# BLDC-M8.net
KiCad netlist of a schematic drawn in Altium Designer
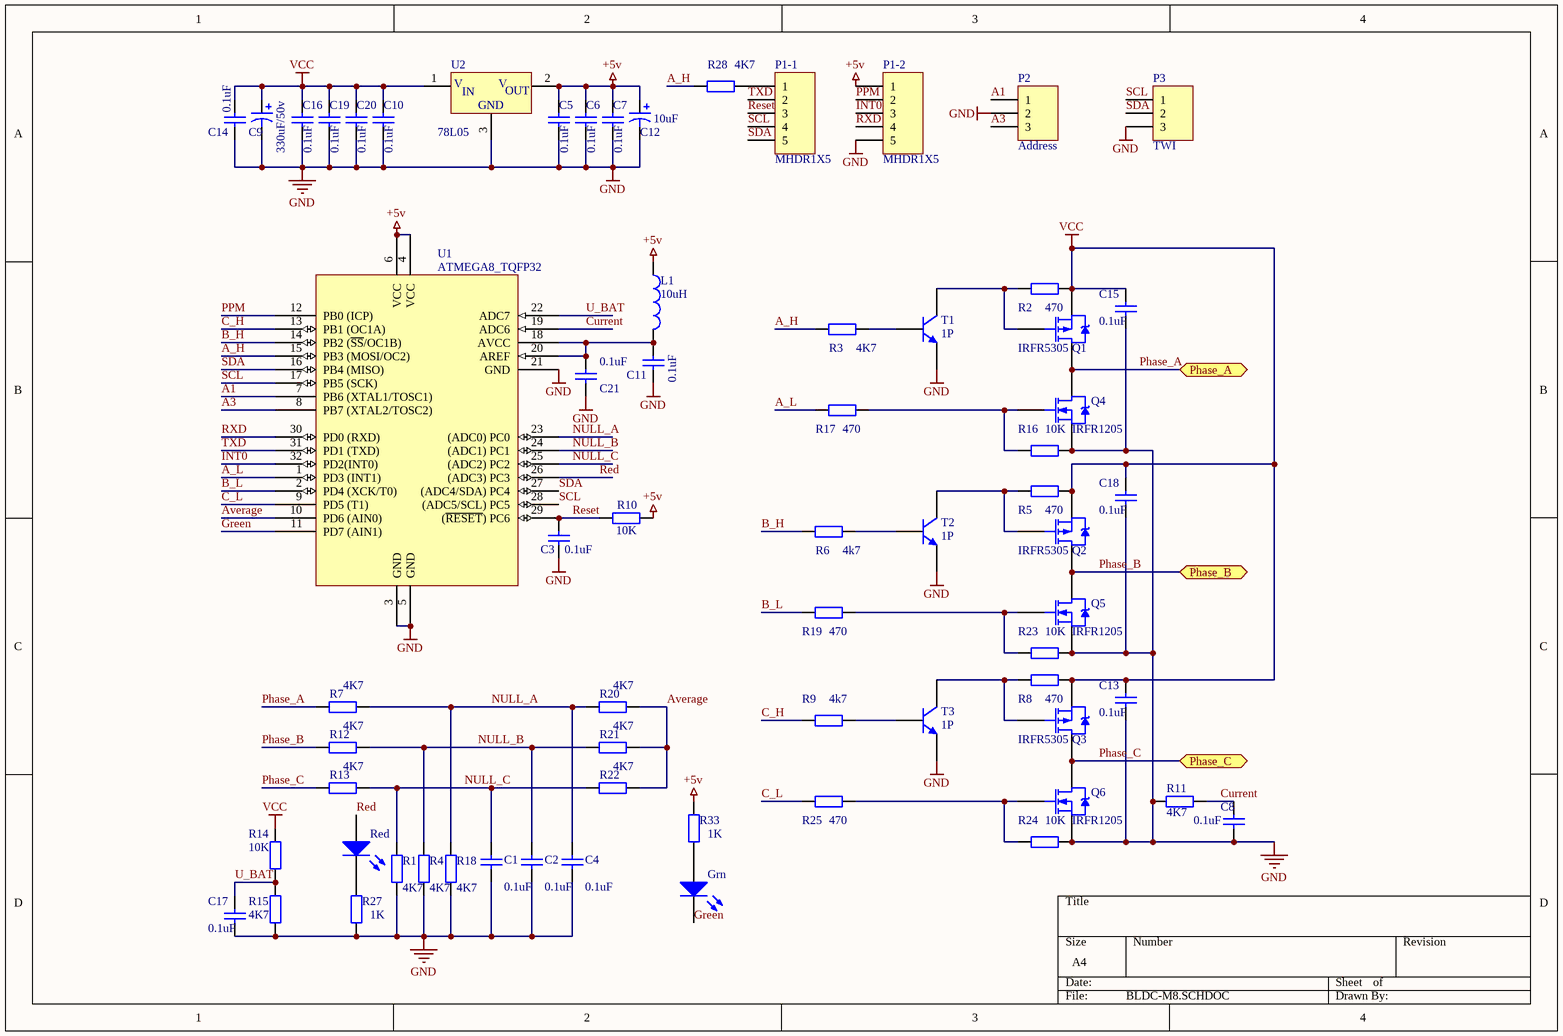
[diagram p0: BLDC-M8.SCHDOC]

(export (version "E")
  (design (tool "Eeschema 10.0.6"))
  (components
    (comp (ref "C1")
      (value "0.1uF")
      (footprint "1608[0603]")
      (description "Capacitor")
      (fields (field (name "Comment") "Cap") (field (name "PUBLISHER") "Altium Limited"))
      (libsource (lib "Miscellaneous Devices") (part "Cap"))
    )
    (comp (ref "C2")
      (value "0.1uF")
      (footprint "1608[0603]")
      (description "Capacitor")
      (fields (field (name "Comment") "Cap") (field (name "PUBLISHER") "Altium Limited"))
      (libsource (lib "Miscellaneous Devices") (part "Cap"))
    )
    (comp (ref "C3")
      (value "0.1uF")
      (footprint "1608[0603]")
      (description "Capacitor")
      (fields (field (name "Comment") "Cap") (field (name "PUBLISHER") "Altium Limited"))
      (libsource (lib "Miscellaneous Devices") (part "Cap"))
    )
    (comp (ref "C4")
      (value "0.1uF")
      (footprint "1608[0603]")
      (description "Capacitor")
      (fields (field (name "Comment") "Cap") (field (name "PUBLISHER") "Altium Limited"))
      (libsource (lib "Miscellaneous Devices") (part "Cap"))
    )
    (comp (ref "C5")
      (value "0.1uF")
      (footprint "1608[0603]")
      (description "Capacitor")
      (fields (field (name "Comment") "Cap") (field (name "PUBLISHER") "Altium Limited"))
      (libsource (lib "Miscellaneous Devices") (part "Cap"))
    )
    (comp (ref "C6")
      (value "0.1uF")
      (footprint "1608[0603]")
      (description "Capacitor")
      (fields (field (name "Comment") "Cap") (field (name "PUBLISHER") "Altium Limited"))
      (libsource (lib "Miscellaneous Devices") (part "Cap"))
    )
    (comp (ref "C7")
      (value "0.1uF")
      (footprint "1608[0603]")
      (description "Capacitor")
      (fields (field (name "Comment") "Cap") (field (name "PUBLISHER") "Altium Limited"))
      (libsource (lib "Miscellaneous Devices") (part "Cap"))
    )
    (comp (ref "C8")
      (value "0.1uF")
      (footprint "1608[0603]")
      (description "Capacitor")
      (fields (field (name "Comment") "Cap") (field (name "PUBLISHER") "Altium Limited"))
      (libsource (lib "Miscellaneous Devices") (part "Cap"))
    )
    (comp (ref "C9")
      (value "330uF/50v")
      (footprint "RAD-0.2")
      (description "Polarized Capacitor (Radial)")
      (fields (field (name "Comment") "Cap Pol1") (field (name "PUBLISHER") "Altium Limited"))
      (libsource (lib "Miscellaneous Devices") (part "Cap Pol1"))
    )
    (comp (ref "C10")
      (value "0.1uF")
      (footprint "1608[0603]")
      (description "Capacitor")
      (fields (field (name "Comment") "Cap") (field (name "PUBLISHER") "Altium Limited"))
      (libsource (lib "Miscellaneous Devices") (part "Cap"))
    )
    (comp (ref "C11")
      (value "0.1uF")
      (footprint "1608[0603]")
      (description "Capacitor")
      (fields (field (name "Comment") "Cap") (field (name "PUBLISHER") "Altium Limited"))
      (libsource (lib "Miscellaneous Devices") (part "Cap"))
    )
    (comp (ref "C12")
      (value "10uF")
      (footprint "3216[1206]")
      (description "Polarized Capacitor (Radial)")
      (fields (field (name "Comment") "Cap Pol1") (field (name "PUBLISHER") "Altium Limited"))
      (libsource (lib "Miscellaneous Devices") (part "Cap Pol1"))
    )
    (comp (ref "C13")
      (value "0.1uF")
      (footprint "1608[0603]")
      (description "Capacitor")
      (fields (field (name "Comment") "Cap") (field (name "PUBLISHER") "Altium Limited"))
      (libsource (lib "Miscellaneous Devices") (part "Cap"))
    )
    (comp (ref "C14")
      (value "0.1uF")
      (footprint "1608[0603]")
      (description "Capacitor")
      (fields (field (name "Comment") "Cap") (field (name "PUBLISHER") "Altium Limited"))
      (libsource (lib "Miscellaneous Devices") (part "Cap"))
    )
    (comp (ref "C15")
      (value "0.1uF")
      (footprint "1608[0603]")
      (description "Capacitor")
      (fields (field (name "Comment") "Cap") (field (name "PUBLISHER") "Altium Limited"))
      (libsource (lib "Miscellaneous Devices") (part "Cap"))
    )
    (comp (ref "C16")
      (value "0.1uF")
      (footprint "1608[0603]")
      (description "Capacitor")
      (fields (field (name "Comment") "Cap") (field (name "PUBLISHER") "Altium Limited"))
      (libsource (lib "Miscellaneous Devices") (part "Cap"))
    )
    (comp (ref "C17")
      (value "0.1uF")
      (footprint "1608[0603]")
      (description "Capacitor")
      (fields (field (name "Comment") "Cap") (field (name "PUBLISHER") "Altium Limited"))
      (libsource (lib "Miscellaneous Devices") (part "Cap"))
    )
    (comp (ref "C18")
      (value "0.1uF")
      (footprint "1608[0603]")
      (description "Capacitor")
      (fields (field (name "Comment") "Cap") (field (name "PUBLISHER") "Altium Limited"))
      (libsource (lib "Miscellaneous Devices") (part "Cap"))
    )
    (comp (ref "C19")
      (value "0.1uF")
      (footprint "1608[0603]")
      (description "Capacitor")
      (fields (field (name "Comment") "Cap") (field (name "PUBLISHER") "Altium Limited"))
      (libsource (lib "Miscellaneous Devices") (part "Cap"))
    )
    (comp (ref "C20")
      (value "0.1uF")
      (footprint "1608[0603]")
      (description "Capacitor")
      (fields (field (name "Comment") "Cap") (field (name "PUBLISHER") "Altium Limited"))
      (libsource (lib "Miscellaneous Devices") (part "Cap"))
    )
    (comp (ref "C21")
      (value "0.1uF")
      (footprint "1608[0603]")
      (description "Capacitor")
      (fields (field (name "Comment") "Cap") (field (name "PUBLISHER") "Altium Limited"))
      (libsource (lib "Miscellaneous Devices") (part "Cap"))
    )
    (comp (ref "Grn")
      (value "LED0")
      (footprint "1608[0603]")
      (description "Typical INFRARED GaAs LED")
      (fields (field (name "PUBLISHER") "Altium Limited"))
      (libsource (lib "Miscellaneous Devices") (part "LED0"))
    )
    (comp (ref "L1")
      (value "10uH")
      (footprint "0402-A")
      (description "Inductor")
      (fields (field (name "PUBLISHER") "Altium Limited"))
      (libsource (lib "Miscellaneous Devices") (part "Inductor"))
    )
    (comp (ref "P1-1")
      (value "MHDR1X5")
      (footprint "MHDR1X5")
      (description "Header, 5-Pin")
      (fields (field (name "PUBLISHER") "Altium Limited"))
      (libsource (lib "Miscellaneous Connectors") (part "MHDR1X5"))
    )
    (comp (ref "P1-2")
      (value "MHDR1X5")
      (footprint "MHDR1X5")
      (description "Header, 5-Pin")
      (fields (field (name "PUBLISHER") "Altium Limited"))
      (libsource (lib "Miscellaneous Connectors") (part "MHDR1X5"))
    )
    (comp (ref "P2")
      (value "Address")
      (footprint "HDR1X3")
      (description "Header, 3-Pin")
      (fields (field (name "PUBLISHER") "Altium Limited"))
      (libsource (lib "Miscellaneous Connectors") (part "Header 3"))
    )
    (comp (ref "P3")
      (value "TWI")
      (footprint "HDR1X3")
      (description "Header, 3-Pin")
      (fields (field (name "PUBLISHER") "Altium Limited"))
      (libsource (lib "Miscellaneous Connectors") (part "Header 3"))
    )
    (comp (ref "Q1")
      (value "IRFR5305")
      (footprint "TO-252AA")
      (description "HEXFET Power MOSFET")
      (fields
        (field (name "MANUFACTURER") "International Rectifier")
        (field (name "PUBLISHER") "Altium Limited")
      )
      (libsource (lib "IR Discrete MOSFET") (part "IRFR5305"))
    )
    (comp (ref "Q2")
      (value "IRFR5305")
      (footprint "SIP-G3/E8")
      (description "HEXFET Power MOSFET")
      (fields
        (field (name "MANUFACTURER") "International Rectifier")
        (field (name "PUBLISHER") "Altium Limited")
      )
      (libsource (lib "IR Discrete MOSFET") (part "IRFR5305"))
    )
    (comp (ref "Q3")
      (value "IRFR5305")
      (footprint "SIP-G3/E8")
      (description "HEXFET Power MOSFET")
      (fields
        (field (name "MANUFACTURER") "International Rectifier")
        (field (name "PUBLISHER") "Altium Limited")
      )
      (libsource (lib "IR Discrete MOSFET") (part "IRFR5305"))
    )
    (comp (ref "Q4")
      (value "IRFR1205")
      (footprint "SIP-G3/E8")
      (description "HEXFET Power MOSFET")
      (fields
        (field (name "MANUFACTURER") "International Rectifier")
        (field (name "PUBLISHER") "Altium Limited")
      )
      (libsource (lib "IR Discrete MOSFET") (part "IRFR1205"))
    )
    (comp (ref "Q5")
      (value "IRFR1205")
      (footprint "SIP-G3/E8")
      (description "HEXFET Power MOSFET")
      (fields
        (field (name "MANUFACTURER") "International Rectifier")
        (field (name "PUBLISHER") "Altium Limited")
      )
      (libsource (lib "IR Discrete MOSFET") (part "IRFR1205"))
    )
    (comp (ref "Q6")
      (value "IRFR1205")
      (footprint "SIP-G3/E8")
      (description "HEXFET Power MOSFET")
      (fields
        (field (name "MANUFACTURER") "International Rectifier")
        (field (name "PUBLISHER") "Altium Limited")
      )
      (libsource (lib "IR Discrete MOSFET") (part "IRFR1205"))
    )
    (comp (ref "R1")
      (value "4K7")
      (footprint "1608[0603]")
      (description "Resistor")
      (fields (field (name "Comment") "Res2") (field (name "PUBLISHER") "Altium Limited"))
      (libsource (lib "") (part "Res2_2"))
    )
    (comp (ref "R2")
      (value "470")
      (footprint "1608[0603]")
      (description "Resistor")
      (fields (field (name "Comment") "Res2") (field (name "PUBLISHER") "Altium Limited"))
      (libsource (lib "Miscellaneous Devices") (part "Res2"))
    )
    (comp (ref "R3")
      (value "4K7")
      (footprint "1608[0603]")
      (description "Resistor")
      (fields (field (name "Comment") "Res2") (field (name "PUBLISHER") "Altium Limited"))
      (libsource (lib "Miscellaneous Devices") (part "Res2"))
    )
    (comp (ref "R4")
      (value "4K7")
      (footprint "1608[0603]")
      (description "Resistor")
      (fields (field (name "Comment") "Res2") (field (name "PUBLISHER") "Altium Limited"))
      (libsource (lib "") (part "Res2_2"))
    )
    (comp (ref "R5")
      (value "470")
      (footprint "1608[0603]")
      (description "Resistor")
      (fields (field (name "Comment") "Res2") (field (name "PUBLISHER") "Altium Limited"))
      (libsource (lib "Miscellaneous Devices") (part "Res2"))
    )
    (comp (ref "R6")
      (value "4k7")
      (footprint "1608[0603]")
      (description "Resistor")
      (fields (field (name "Comment") "Res2") (field (name "PUBLISHER") "Altium Limited"))
      (libsource (lib "Miscellaneous Devices") (part "Res2"))
    )
    (comp (ref "R7")
      (value "4K7")
      (footprint "1608[0603]")
      (description "Resistor")
      (fields (field (name "Comment") "Res2") (field (name "PUBLISHER") "Altium Limited"))
      (libsource (lib "Miscellaneous Devices") (part "Res2"))
    )
    (comp (ref "R8")
      (value "470")
      (footprint "1608[0603]")
      (description "Resistor")
      (fields (field (name "Comment") "Res2") (field (name "PUBLISHER") "Altium Limited"))
      (libsource (lib "Miscellaneous Devices") (part "Res2"))
    )
    (comp (ref "R9")
      (value "4k7")
      (footprint "1608[0603]")
      (description "Resistor")
      (fields (field (name "Comment") "Res2") (field (name "PUBLISHER") "Altium Limited"))
      (libsource (lib "Miscellaneous Devices") (part "Res2"))
    )
    (comp (ref "R10")
      (value "10K")
      (footprint "1608[0603]")
      (description "Resistor")
      (fields (field (name "Comment") "Res2") (field (name "PUBLISHER") "Altium Limited"))
      (libsource (lib "Miscellaneous Devices") (part "Res2"))
    )
    (comp (ref "R11")
      (value "4K7")
      (footprint "1608[0603]")
      (description "Resistor")
      (fields (field (name "Comment") "Res2") (field (name "PUBLISHER") "Altium Limited"))
      (libsource (lib "") (part "Res2_1"))
    )
    (comp (ref "R12")
      (value "4K7")
      (footprint "1608[0603]")
      (description "Resistor")
      (fields (field (name "Comment") "Res2") (field (name "PUBLISHER") "Altium Limited"))
      (libsource (lib "Miscellaneous Devices") (part "Res2"))
    )
    (comp (ref "R13")
      (value "4K7")
      (footprint "1608[0603]")
      (description "Resistor")
      (fields (field (name "Comment") "Res2") (field (name "PUBLISHER") "Altium Limited"))
      (libsource (lib "Miscellaneous Devices") (part "Res2"))
    )
    (comp (ref "R14")
      (value "10K")
      (footprint "1608[0603]")
      (description "Resistor")
      (fields (field (name "Comment") "Res2") (field (name "PUBLISHER") "Altium Limited"))
      (libsource (lib "") (part "Res2_2"))
    )
    (comp (ref "R15")
      (value "4K7")
      (footprint "1608[0603]")
      (description "Resistor")
      (fields (field (name "Comment") "Res2") (field (name "PUBLISHER") "Altium Limited"))
      (libsource (lib "") (part "Res2_2"))
    )
    (comp (ref "R16")
      (value "10K")
      (footprint "1608[0603]")
      (description "Resistor")
      (fields (field (name "Comment") "Res2") (field (name "PUBLISHER") "Altium Limited"))
      (libsource (lib "Miscellaneous Devices") (part "Res2"))
    )
    (comp (ref "R17")
      (value "470")
      (footprint "1608[0603]")
      (description "Resistor")
      (fields (field (name "Comment") "Res2") (field (name "PUBLISHER") "Altium Limited"))
      (libsource (lib "Miscellaneous Devices") (part "Res2"))
    )
    (comp (ref "R18")
      (value "4K7")
      (footprint "1608[0603]")
      (description "Resistor")
      (fields (field (name "Comment") "Res2") (field (name "PUBLISHER") "Altium Limited"))
      (libsource (lib "") (part "Res2_2"))
    )
    (comp (ref "R19")
      (value "470")
      (footprint "1608[0603]")
      (description "Resistor")
      (fields (field (name "Comment") "Res2") (field (name "PUBLISHER") "Altium Limited"))
      (libsource (lib "Miscellaneous Devices") (part "Res2"))
    )
    (comp (ref "R20")
      (value "4K7")
      (footprint "1608[0603]")
      (description "Resistor")
      (fields (field (name "Comment") "Res2") (field (name "PUBLISHER") "Altium Limited"))
      (libsource (lib "Miscellaneous Devices") (part "Res2"))
    )
    (comp (ref "R21")
      (value "4K7")
      (footprint "1608[0603]")
      (description "Resistor")
      (fields (field (name "Comment") "Res2") (field (name "PUBLISHER") "Altium Limited"))
      (libsource (lib "Miscellaneous Devices") (part "Res2"))
    )
    (comp (ref "R22")
      (value "4K7")
      (footprint "1608[0603]")
      (description "Resistor")
      (fields (field (name "Comment") "Res2") (field (name "PUBLISHER") "Altium Limited"))
      (libsource (lib "Miscellaneous Devices") (part "Res2"))
    )
    (comp (ref "R23")
      (value "10K")
      (footprint "1608[0603]")
      (description "Resistor")
      (fields (field (name "Comment") "Res2") (field (name "PUBLISHER") "Altium Limited"))
      (libsource (lib "Miscellaneous Devices") (part "Res2"))
    )
    (comp (ref "R24")
      (value "10K")
      (footprint "1608[0603]")
      (description "Resistor")
      (fields (field (name "Comment") "Res2") (field (name "PUBLISHER") "Altium Limited"))
      (libsource (lib "Miscellaneous Devices") (part "Res2"))
    )
    (comp (ref "R25")
      (value "470")
      (footprint "1608[0603]")
      (description "Resistor")
      (fields (field (name "Comment") "Res2") (field (name "PUBLISHER") "Altium Limited"))
      (libsource (lib "Miscellaneous Devices") (part "Res2"))
    )
    (comp (ref "R27")
      (value "1K")
      (footprint "1608[0603]")
      (description "Resistor")
      (fields (field (name "Comment") "Res2") (field (name "PUBLISHER") "Altium Limited"))
      (libsource (lib "") (part "Res2_2"))
    )
    (comp (ref "R28")
      (value "4K7")
      (footprint "1608[0603]")
      (description "Resistor")
      (fields (field (name "Comment") "Res2") (field (name "PUBLISHER") "Altium Limited"))
      (libsource (lib "Miscellaneous Devices") (part "Res2"))
    )
    (comp (ref "R33")
      (value "1K")
      (footprint "1608[0603]")
      (description "Resistor")
      (fields (field (name "Comment") "Res2") (field (name "PUBLISHER") "Altium Limited"))
      (libsource (lib "") (part "Res2_2"))
    )
    (comp (ref "Red")
      (value "LED0")
      (footprint "Miscellaneous Devices:1608[0603]")
      (description "Typical INFRARED GaAs LED")
      (fields (field (name "PUBLISHER") "Altium Limited"))
      (libsource (lib "Miscellaneous Devices") (part "LED0"))
    )
    (comp (ref "T1")
      (value "1P")
      (footprint "SOT-23")
      (description "NPN General Purpose Amplifier")
      (fields (field (name "PUBLISHER") "Altium Limited"))
      (libsource (lib "Miscellaneous Devices") (part "2N3904"))
    )
    (comp (ref "T2")
      (value "1P")
      (footprint "SOT-23")
      (description "NPN General Purpose Amplifier")
      (fields (field (name "PUBLISHER") "Altium Limited"))
      (libsource (lib "Miscellaneous Devices") (part "2N3904"))
    )
    (comp (ref "T3")
      (value "1P")
      (footprint "SOT-23")
      (description "NPN General Purpose Amplifier")
      (fields (field (name "PUBLISHER") "Altium Limited"))
      (libsource (lib "Miscellaneous Devices") (part "2N3904"))
    )
    (comp (ref "U1")
      (value "ATMEGA8_TQFP32")
      (footprint "LQFP32")
      (description "Atmel Microcontroller - Library created by carel..  <www.mpfreezone.com>")
      (libsource (lib "avr_protel") (part "ATMEGA8_TQFP32"))
    )
    (comp (ref "U2")
      (value "78L05")
      (footprint "AMS1117")
      (description "3-Terminal Positive Voltage Regulator")
      (libsource (lib "稳压器件") (part "78L05"))
    )
  )
  (nets
    (net (code "1") (name "+5v") (class "Default")
      (node (ref "C12") (pin "1") (pinfunction "1_1") (pintype "passive"))
      (node (ref "C5") (pin "1") (pinfunction "1_1") (pintype "passive"))
      (node (ref "C6") (pin "1") (pinfunction "1_1") (pintype "passive"))
      (node (ref "C7") (pin "1") (pinfunction "1_1") (pintype "passive"))
      (node (ref "L1") (pin "1") (pinfunction "1_1") (pintype "passive"))
      (node (ref "P1-2") (pin "1") (pinfunction "1_1") (pintype "passive"))
      (node (ref "R10") (pin "2") (pinfunction "2_2") (pintype "passive"))
      (node (ref "R33") (pin "2") (pinfunction "2_2") (pintype "passive"))
      (node (ref "U1") (pin "4") (pinfunction "VCC_4") (pintype "power_in"))
      (node (ref "U1") (pin "6") (pinfunction "VCC_6") (pintype "passive"))
      (node (ref "U2") (pin "2") (pinfunction "VOUT_2") (pintype "passive"))
    )
    (net (code "2") (name "/A1") (class "Default")
      (node (ref "P2") (pin "1") (pinfunction "1_1") (pintype "passive"))
      (node (ref "U1") (pin "7") (pinfunction "PB6_(XTAL1/TOSC1)_7") (pintype "passive"))
    )
    (net (code "3") (name "/A3") (class "Default")
      (node (ref "P2") (pin "3") (pinfunction "3_3") (pintype "passive"))
      (node (ref "U1") (pin "8") (pinfunction "PB7_(XTAL2/TOSC2)_8") (pintype "passive"))
    )
    (net (code "4") (name "/A_H") (class "Default")
      (node (ref "R28") (pin "1") (pinfunction "1_1") (pintype "passive"))
      (node (ref "R3") (pin "1") (pinfunction "1_1") (pintype "passive"))
      (node (ref "U1") (pin "15") (pinfunction "PB3_(MOSI/OC2)_15") (pintype "bidirectional"))
    )
    (net (code "5") (name "/A_L") (class "Default")
      (node (ref "R17") (pin "1") (pinfunction "1_1") (pintype "passive"))
      (node (ref "U1") (pin "1") (pinfunction "PD3_(INT1)_1") (pintype "bidirectional"))
    )
    (net (code "6") (name "/Average") (class "Default")
      (node (ref "R20") (pin "2") (pinfunction "2_2") (pintype "passive"))
      (node (ref "R21") (pin "2") (pinfunction "2_2") (pintype "passive"))
      (node (ref "R22") (pin "2") (pinfunction "2_2") (pintype "passive"))
      (node (ref "U1") (pin "10") (pinfunction "PD6_(AIN0)_10") (pintype "passive"))
    )
    (net (code "7") (name "/B_H") (class "Default")
      (node (ref "R6") (pin "1") (pinfunction "1_1") (pintype "passive"))
      (node (ref "U1") (pin "14") (pinfunction "PB2_(~{SS}/OC1B)_14") (pintype "bidirectional"))
    )
    (net (code "8") (name "/B_L") (class "Default")
      (node (ref "R19") (pin "1") (pinfunction "1_1") (pintype "passive"))
      (node (ref "U1") (pin "2") (pinfunction "PD4_(XCK/T0)_2") (pintype "bidirectional"))
    )
    (net (code "9") (name "/C_H") (class "Default")
      (node (ref "R9") (pin "1") (pinfunction "1_1") (pintype "passive"))
      (node (ref "U1") (pin "13") (pinfunction "PB1_(OC1A)_13") (pintype "bidirectional"))
    )
    (net (code "10") (name "/C_L") (class "Default")
      (node (ref "R25") (pin "1") (pinfunction "1_1") (pintype "passive"))
      (node (ref "U1") (pin "9") (pinfunction "PD5_(T1)_9") (pintype "passive"))
    )
    (net (code "11") (name "/Current") (class "Default")
      (node (ref "C8") (pin "1") (pinfunction "1_1") (pintype "passive"))
      (node (ref "R11") (pin "1") (pinfunction "1_1") (pintype "passive"))
      (node (ref "U1") (pin "19") (pinfunction "ADC6_19") (pintype "input"))
    )
    (net (code "12") (name "/Green") (class "Default")
      (node (ref "Grn") (pin "2") (pinfunction "K_2") (pintype "passive"))
      (node (ref "U1") (pin "11") (pinfunction "PD7_(AIN1)_11") (pintype "passive"))
    )
    (net (code "13") (name "/INT0") (class "Default")
      (node (ref "P1-2") (pin "3") (pinfunction "3_3") (pintype "passive"))
      (node (ref "U1") (pin "32") (pinfunction "PD2(INT0)_32") (pintype "bidirectional"))
    )
    (net (code "14") (name "/NULL_A") (class "Default")
      (node (ref "C4") (pin "2") (pinfunction "2_2") (pintype "passive"))
      (node (ref "R18") (pin "2") (pinfunction "2_2") (pintype "passive"))
      (node (ref "R20") (pin "1") (pinfunction "1_1") (pintype "passive"))
      (node (ref "R7") (pin "2") (pinfunction "2_2") (pintype "passive"))
      (node (ref "U1") (pin "23") (pinfunction "(ADC0)_PC0_23") (pintype "bidirectional"))
    )
    (net (code "15") (name "/NULL_B") (class "Default")
      (node (ref "C2") (pin "2") (pinfunction "2_2") (pintype "passive"))
      (node (ref "R12") (pin "2") (pinfunction "2_2") (pintype "passive"))
      (node (ref "R21") (pin "1") (pinfunction "1_1") (pintype "passive"))
      (node (ref "R4") (pin "2") (pinfunction "2_2") (pintype "passive"))
      (node (ref "U1") (pin "24") (pinfunction "(ADC1)_PC1_24") (pintype "bidirectional"))
    )
    (net (code "16") (name "/NULL_C") (class "Default")
      (node (ref "C1") (pin "2") (pinfunction "2_2") (pintype "passive"))
      (node (ref "R1") (pin "2") (pinfunction "2_2") (pintype "passive"))
      (node (ref "R13") (pin "2") (pinfunction "2_2") (pintype "passive"))
      (node (ref "R22") (pin "1") (pinfunction "1_1") (pintype "passive"))
      (node (ref "U1") (pin "25") (pinfunction "(ADC2)_PC2_25") (pintype "bidirectional"))
    )
    (net (code "17") (name "/PPM") (class "Default")
      (node (ref "P1-2") (pin "2") (pinfunction "2_2") (pintype "passive"))
      (node (ref "U1") (pin "12") (pinfunction "PB0_(ICP)_12") (pintype "passive"))
    )
    (net (code "18") (name "/Phase_A") (class "Default")
      (node (ref "Q1") (pin "4") (pinfunction "D_4") (pintype "passive"))
      (node (ref "Q4") (pin "4") (pinfunction "D_4") (pintype "passive"))
      (node (ref "R7") (pin "1") (pinfunction "1_1") (pintype "passive"))
    )
    (net (code "19") (name "/Phase_B") (class "Default")
      (node (ref "Q2") (pin "4") (pinfunction "D_4") (pintype "passive"))
      (node (ref "Q5") (pin "4") (pinfunction "D_4") (pintype "passive"))
      (node (ref "R12") (pin "1") (pinfunction "1_1") (pintype "passive"))
    )
    (net (code "20") (name "/Phase_C") (class "Default")
      (node (ref "Q3") (pin "4") (pinfunction "D_4") (pintype "passive"))
      (node (ref "Q6") (pin "4") (pinfunction "D_4") (pintype "passive"))
      (node (ref "R13") (pin "1") (pinfunction "1_1") (pintype "passive"))
    )
    (net (code "21") (name "/RXD") (class "Default")
      (node (ref "P1-2") (pin "4") (pinfunction "4_4") (pintype "passive"))
      (node (ref "U1") (pin "30") (pinfunction "PD0_(RXD)_30") (pintype "bidirectional"))
    )
    (net (code "22") (name "/Red") (class "Default")
      (node (ref "Red") (pin "1") (pinfunction "A_1") (pintype "passive"))
      (node (ref "U1") (pin "26") (pinfunction "(ADC3)_PC3_26") (pintype "bidirectional"))
    )
    (net (code "23") (name "/Reset") (class "Default")
      (node (ref "C3") (pin "1") (pinfunction "1_1") (pintype "passive"))
      (node (ref "P1-1") (pin "3") (pinfunction "3_3") (pintype "passive"))
      (node (ref "R10") (pin "1") (pinfunction "1_1") (pintype "passive"))
      (node (ref "U1") (pin "29") (pinfunction "(~{RESET})_PC6_29") (pintype "bidirectional"))
    )
    (net (code "24") (name "/SCL") (class "Default")
      (node (ref "P1-1") (pin "4") (pinfunction "4_4") (pintype "passive"))
      (node (ref "P3") (pin "1") (pinfunction "1_1") (pintype "passive"))
      (node (ref "U1") (pin "17") (pinfunction "PB5_(SCK)_17") (pintype "bidirectional"))
      (node (ref "U1") (pin "28") (pinfunction "(ADC5/SCL)_PC5_28") (pintype "bidirectional"))
    )
    (net (code "25") (name "/SDA") (class "Default")
      (node (ref "P1-1") (pin "5") (pinfunction "5_5") (pintype "passive"))
      (node (ref "P3") (pin "2") (pinfunction "2_2") (pintype "passive"))
      (node (ref "U1") (pin "16") (pinfunction "PB4_(MISO)_16") (pintype "bidirectional"))
      (node (ref "U1") (pin "27") (pinfunction "(ADC4/SDA)_PC4_27") (pintype "bidirectional"))
    )
    (net (code "26") (name "/TXD") (class "Default")
      (node (ref "P1-1") (pin "2") (pinfunction "2_2") (pintype "passive"))
      (node (ref "U1") (pin "31") (pinfunction "PD1_(TXD)_31") (pintype "bidirectional"))
    )
    (net (code "27") (name "/U_BAT") (class "Default")
      (node (ref "C17") (pin "1") (pinfunction "1_1") (pintype "passive"))
      (node (ref "R14") (pin "1") (pinfunction "1_1") (pintype "passive"))
      (node (ref "R15") (pin "2") (pinfunction "2_2") (pintype "passive"))
      (node (ref "U1") (pin "22") (pinfunction "ADC7_22") (pintype "input"))
    )
    (net (code "28") (name "GND") (class "Default")
      (node (ref "C1") (pin "1") (pinfunction "1_1") (pintype "passive"))
      (node (ref "C10") (pin "2") (pinfunction "2_2") (pintype "passive"))
      (node (ref "C11") (pin "2") (pinfunction "2_2") (pintype "passive"))
      (node (ref "C12") (pin "2") (pinfunction "2_2") (pintype "passive"))
      (node (ref "C13") (pin "1") (pinfunction "1_1") (pintype "passive"))
      (node (ref "C14") (pin "1") (pinfunction "1_1") (pintype "passive"))
      (node (ref "C15") (pin "1") (pinfunction "1_1") (pintype "passive"))
      (node (ref "C16") (pin "2") (pinfunction "2_2") (pintype "passive"))
      (node (ref "C17") (pin "2") (pinfunction "2_2") (pintype "passive"))
      (node (ref "C18") (pin "1") (pinfunction "1_1") (pintype "passive"))
      (node (ref "C19") (pin "2") (pinfunction "2_2") (pintype "passive"))
      (node (ref "C2") (pin "1") (pinfunction "1_1") (pintype "passive"))
      (node (ref "C20") (pin "2") (pinfunction "2_2") (pintype "passive"))
      (node (ref "C21") (pin "2") (pinfunction "2_2") (pintype "passive"))
      (node (ref "C3") (pin "2") (pinfunction "2_2") (pintype "passive"))
      (node (ref "C4") (pin "1") (pinfunction "1_1") (pintype "passive"))
      (node (ref "C5") (pin "2") (pinfunction "2_2") (pintype "passive"))
      (node (ref "C6") (pin "2") (pinfunction "2_2") (pintype "passive"))
      (node (ref "C7") (pin "2") (pinfunction "2_2") (pintype "passive"))
      (node (ref "C8") (pin "2") (pinfunction "2_2") (pintype "passive"))
      (node (ref "C9") (pin "2") (pinfunction "2_2") (pintype "passive"))
      (node (ref "P1-2") (pin "5") (pinfunction "5_5") (pintype "passive"))
      (node (ref "P2") (pin "2") (pinfunction "2_2") (pintype "passive"))
      (node (ref "P3") (pin "3") (pinfunction "3_3") (pintype "passive"))
      (node (ref "Q4") (pin "3") (pinfunction "S_3") (pintype "passive"))
      (node (ref "Q5") (pin "3") (pinfunction "S_3") (pintype "passive"))
      (node (ref "Q6") (pin "3") (pinfunction "S_3") (pintype "passive"))
      (node (ref "R1") (pin "1") (pinfunction "1_1") (pintype "passive"))
      (node (ref "R11") (pin "2") (pinfunction "2_2") (pintype "passive"))
      (node (ref "R15") (pin "1") (pinfunction "1_1") (pintype "passive"))
      (node (ref "R16") (pin "2") (pinfunction "2_2") (pintype "passive"))
      (node (ref "R18") (pin "1") (pinfunction "1_1") (pintype "passive"))
      (node (ref "R23") (pin "2") (pinfunction "2_2") (pintype "passive"))
      (node (ref "R24") (pin "2") (pinfunction "2_2") (pintype "passive"))
      (node (ref "R27") (pin "1") (pinfunction "1_1") (pintype "passive"))
      (node (ref "R4") (pin "1") (pinfunction "1_1") (pintype "passive"))
      (node (ref "T1") (pin "1") (pinfunction "E_1") (pintype "passive"))
      (node (ref "T2") (pin "1") (pinfunction "E_1") (pintype "passive"))
      (node (ref "T3") (pin "1") (pinfunction "E_1") (pintype "passive"))
      (node (ref "U1") (pin "21") (pinfunction "GND_21") (pintype "passive"))
      (node (ref "U1") (pin "3") (pinfunction "GND_3") (pintype "passive"))
      (node (ref "U1") (pin "5") (pinfunction "GND_5") (pintype "power_in"))
      (node (ref "U2") (pin "3") (pinfunction "GND_3") (pintype "passive"))
    )
    (net (code "29") (name "Net-(Grn-A)") (class "Default")
      (node (ref "Grn") (pin "1") (pinfunction "A_1") (pintype "passive"))
      (node (ref "R33") (pin "1") (pinfunction "1_1") (pintype "passive"))
    )
    (net (code "30") (name "Net-(P1-1-Pad1)") (class "Default")
      (node (ref "P1-1") (pin "1") (pinfunction "1_1") (pintype "passive"))
      (node (ref "R28") (pin "2") (pinfunction "2_2") (pintype "passive"))
    )
    (net (code "31") (name "Net-(Q1-G)") (class "Default")
      (node (ref "Q1") (pin "1") (pinfunction "G_1") (pintype "passive"))
      (node (ref "R2") (pin "1") (pinfunction "1_1") (pintype "passive"))
      (node (ref "T1") (pin "3") (pinfunction "C_3") (pintype "passive"))
    )
    (net (code "32") (name "Net-(Q2-G)") (class "Default")
      (node (ref "Q2") (pin "1") (pinfunction "G_1") (pintype "passive"))
      (node (ref "R5") (pin "1") (pinfunction "1_1") (pintype "passive"))
      (node (ref "T2") (pin "3") (pinfunction "C_3") (pintype "passive"))
    )
    (net (code "33") (name "Net-(Q3-G)") (class "Default")
      (node (ref "Q3") (pin "1") (pinfunction "G_1") (pintype "passive"))
      (node (ref "R8") (pin "1") (pinfunction "1_1") (pintype "passive"))
      (node (ref "T3") (pin "3") (pinfunction "C_3") (pintype "passive"))
    )
    (net (code "34") (name "Net-(Q4-G)") (class "Default")
      (node (ref "Q4") (pin "1") (pinfunction "G_1") (pintype "passive"))
      (node (ref "R16") (pin "1") (pinfunction "1_1") (pintype "passive"))
      (node (ref "R17") (pin "2") (pinfunction "2_2") (pintype "passive"))
    )
    (net (code "35") (name "Net-(Q5-G)") (class "Default")
      (node (ref "Q5") (pin "1") (pinfunction "G_1") (pintype "passive"))
      (node (ref "R19") (pin "2") (pinfunction "2_2") (pintype "passive"))
      (node (ref "R23") (pin "1") (pinfunction "1_1") (pintype "passive"))
    )
    (net (code "36") (name "Net-(Q6-G)") (class "Default")
      (node (ref "Q6") (pin "1") (pinfunction "G_1") (pintype "passive"))
      (node (ref "R24") (pin "1") (pinfunction "1_1") (pintype "passive"))
      (node (ref "R25") (pin "2") (pinfunction "2_2") (pintype "passive"))
    )
    (net (code "37") (name "Net-(Red-K)") (class "Default")
      (node (ref "R27") (pin "2") (pinfunction "2_2") (pintype "passive"))
      (node (ref "Red") (pin "2") (pinfunction "K_2") (pintype "passive"))
    )
    (net (code "38") (name "Net-(T1-B)") (class "Default")
      (node (ref "R3") (pin "2") (pinfunction "2_2") (pintype "passive"))
      (node (ref "T1") (pin "2") (pinfunction "B_2") (pintype "passive"))
    )
    (net (code "39") (name "Net-(T2-B)") (class "Default")
      (node (ref "R6") (pin "2") (pinfunction "2_2") (pintype "passive"))
      (node (ref "T2") (pin "2") (pinfunction "B_2") (pintype "passive"))
    )
    (net (code "40") (name "Net-(T3-B)") (class "Default")
      (node (ref "R9") (pin "2") (pinfunction "2_2") (pintype "passive"))
      (node (ref "T3") (pin "2") (pinfunction "B_2") (pintype "passive"))
    )
    (net (code "41") (name "Net-(U1-AREF)") (class "Default")
      (node (ref "C11") (pin "1") (pinfunction "1_1") (pintype "passive"))
      (node (ref "C21") (pin "1") (pinfunction "1_1") (pintype "passive"))
      (node (ref "L1") (pin "2") (pinfunction "2_2") (pintype "passive"))
      (node (ref "U1") (pin "18") (pinfunction "AVCC_18") (pintype "passive"))
      (node (ref "U1") (pin "20") (pinfunction "AREF_20") (pintype "input"))
    )
    (net (code "42") (name "VCC") (class "Default")
      (node (ref "C10") (pin "1") (pinfunction "1_1") (pintype "passive"))
      (node (ref "C13") (pin "2") (pinfunction "2_2") (pintype "passive"))
      (node (ref "C14") (pin "2") (pinfunction "2_2") (pintype "passive"))
      (node (ref "C15") (pin "2") (pinfunction "2_2") (pintype "passive"))
      (node (ref "C16") (pin "1") (pinfunction "1_1") (pintype "passive"))
      (node (ref "C18") (pin "2") (pinfunction "2_2") (pintype "passive"))
      (node (ref "C19") (pin "1") (pinfunction "1_1") (pintype "passive"))
      (node (ref "C20") (pin "1") (pinfunction "1_1") (pintype "passive"))
      (node (ref "C9") (pin "1") (pinfunction "1_1") (pintype "passive"))
      (node (ref "Q1") (pin "3") (pinfunction "S_3") (pintype "passive"))
      (node (ref "Q2") (pin "3") (pinfunction "S_3") (pintype "passive"))
      (node (ref "Q3") (pin "3") (pinfunction "S_3") (pintype "passive"))
      (node (ref "R14") (pin "2") (pinfunction "2_2") (pintype "passive"))
      (node (ref "R2") (pin "2") (pinfunction "2_2") (pintype "passive"))
      (node (ref "R5") (pin "2") (pinfunction "2_2") (pintype "passive"))
      (node (ref "R8") (pin "2") (pinfunction "2_2") (pintype "passive"))
      (node (ref "U2") (pin "1") (pinfunction "VIN_1") (pintype "passive"))
    )
  )
)
